# TENG.net
KiCad netlist of a schematic drawn in Altium Designer
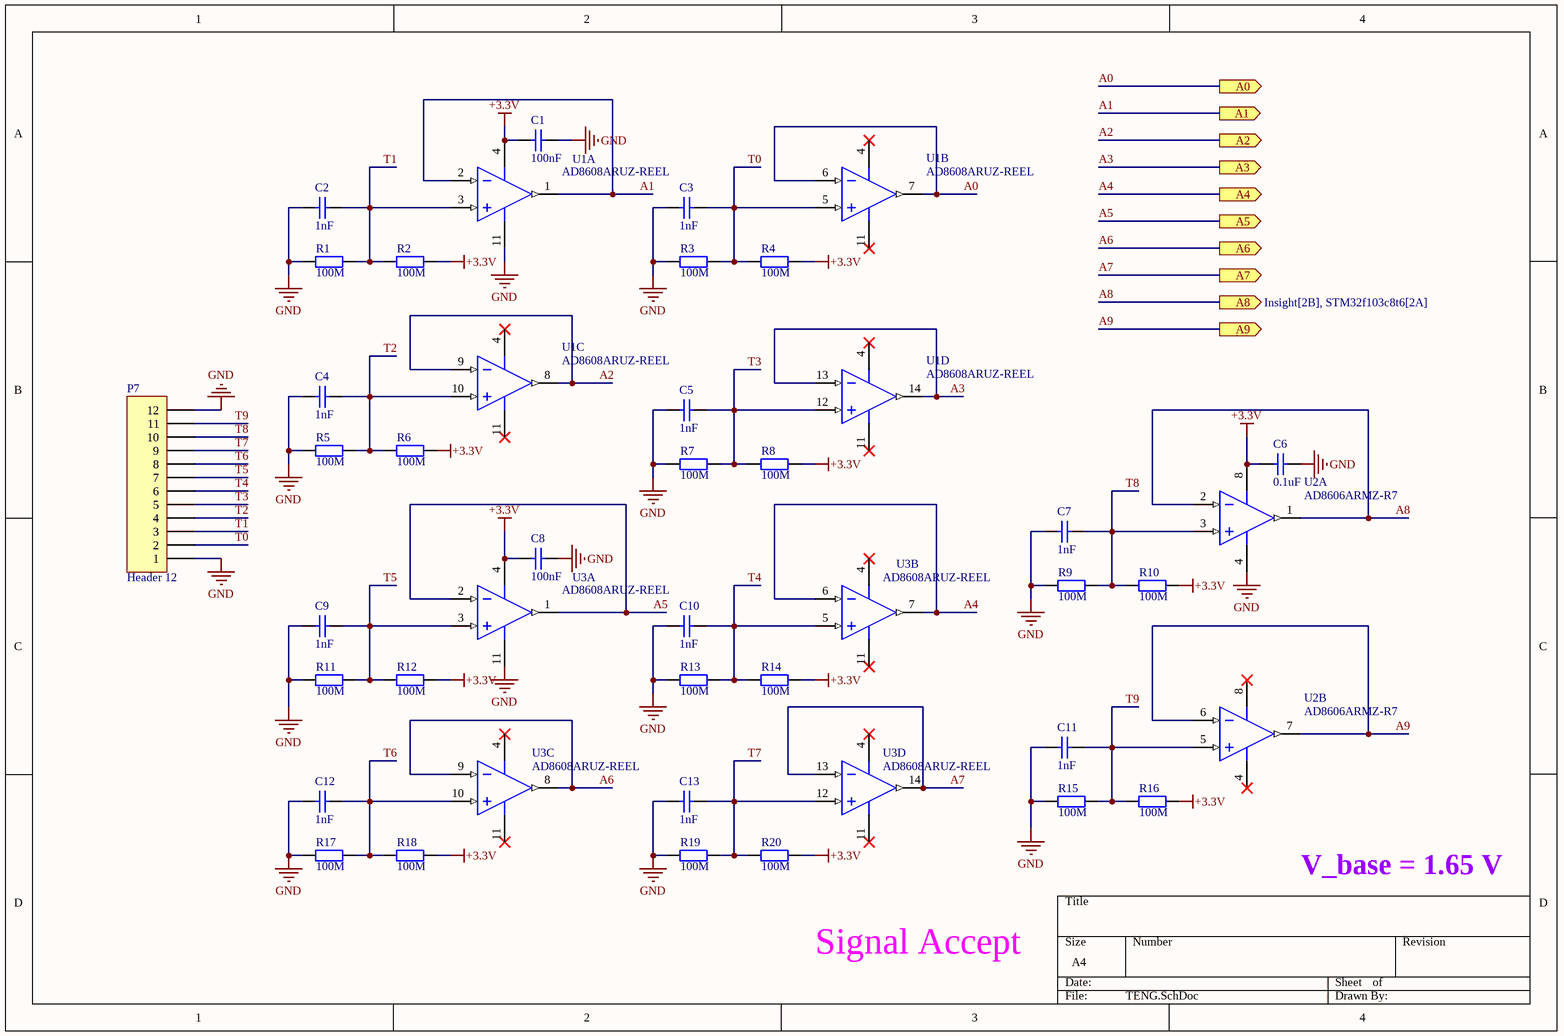
[diagram p0: TENG.SchDoc]

(export (version "E")
  (design (tool "Eeschema 10.0.6"))
  (components
    (comp (ref "C1")
      (value "100nF")
      (footprint "0402_C")
      (description "0402贴片电容")
      (libsource (lib "02-Miscellaneous_Devices_ZSF_Library") (part "Cap_0402"))
    )
    (comp (ref "C2")
      (value "1nF")
      (footprint "0402_C")
      (description "0402贴片电容")
      (libsource (lib "02-Miscellaneous_Devices_ZSF_Library") (part "Cap_0402"))
    )
    (comp (ref "C3")
      (value "1nF")
      (footprint "0402_C")
      (description "0402贴片电容")
      (libsource (lib "02-Miscellaneous_Devices_ZSF_Library") (part "Cap_0402"))
    )
    (comp (ref "C4")
      (value "1nF")
      (footprint "0402_C")
      (description "0402贴片电容")
      (libsource (lib "02-Miscellaneous_Devices_ZSF_Library") (part "Cap_0402"))
    )
    (comp (ref "C5")
      (value "1nF")
      (footprint "0402_C")
      (description "0402贴片电容")
      (libsource (lib "02-Miscellaneous_Devices_ZSF_Library") (part "Cap_0402"))
    )
    (comp (ref "C6")
      (value "0.1uF")
      (footprint "0402_C")
      (description "0402贴片电容")
      (libsource (lib "02-Miscellaneous_Devices_ZSF_Library") (part "Cap_0402"))
    )
    (comp (ref "C7")
      (value "1nF")
      (footprint "0402_C")
      (description "0402贴片电容")
      (libsource (lib "02-Miscellaneous_Devices_ZSF_Library") (part "Cap_0402"))
    )
    (comp (ref "C8")
      (value "100nF")
      (footprint "0402_C")
      (description "0402贴片电容")
      (libsource (lib "02-Miscellaneous_Devices_ZSF_Library") (part "Cap_0402"))
    )
    (comp (ref "C9")
      (value "1nF")
      (footprint "0402_C")
      (description "0402贴片电容")
      (libsource (lib "02-Miscellaneous_Devices_ZSF_Library") (part "Cap_0402"))
    )
    (comp (ref "C10")
      (value "1nF")
      (footprint "0402_C")
      (description "0402贴片电容")
      (libsource (lib "02-Miscellaneous_Devices_ZSF_Library") (part "Cap_0402"))
    )
    (comp (ref "C11")
      (value "1nF")
      (footprint "0402_C")
      (description "0402贴片电容")
      (libsource (lib "02-Miscellaneous_Devices_ZSF_Library") (part "Cap_0402"))
    )
    (comp (ref "C12")
      (value "1nF")
      (footprint "0402_C")
      (description "0402贴片电容")
      (libsource (lib "02-Miscellaneous_Devices_ZSF_Library") (part "Cap_0402"))
    )
    (comp (ref "C13")
      (value "1nF")
      (footprint "0402_C")
      (description "0402贴片电容")
      (libsource (lib "02-Miscellaneous_Devices_ZSF_Library") (part "Cap_0402"))
    )
    (comp (ref "P7")
      (value "Header 12")
      (footprint "HDR1X12")
      (description "Header, 12-Pin")
      (fields (field (name "PUBLISHER") "Altium Limited"))
      (libsource (lib "03-EButterflyIntegratedLibrary") (part "Header 12"))
    )
    (comp (ref "R1")
      (value "100M")
      (footprint "0402_R")
      (description "贴片电阻")
      (libsource (lib "02-Miscellaneous_Devices_ZSF_Library") (part "Res_0402"))
    )
    (comp (ref "R2")
      (value "100M")
      (footprint "0402_R")
      (description "贴片电阻")
      (libsource (lib "02-Miscellaneous_Devices_ZSF_Library") (part "Res_0402"))
    )
    (comp (ref "R3")
      (value "100M")
      (footprint "0402_R")
      (description "贴片电阻")
      (libsource (lib "02-Miscellaneous_Devices_ZSF_Library") (part "Res_0402"))
    )
    (comp (ref "R4")
      (value "100M")
      (footprint "0402_R")
      (description "贴片电阻")
      (libsource (lib "02-Miscellaneous_Devices_ZSF_Library") (part "Res_0402"))
    )
    (comp (ref "R5")
      (value "100M")
      (footprint "0402_R")
      (description "贴片电阻")
      (libsource (lib "02-Miscellaneous_Devices_ZSF_Library") (part "Res_0402"))
    )
    (comp (ref "R6")
      (value "100M")
      (footprint "0402_R")
      (description "贴片电阻")
      (libsource (lib "02-Miscellaneous_Devices_ZSF_Library") (part "Res_0402"))
    )
    (comp (ref "R7")
      (value "100M")
      (footprint "0402_R")
      (description "贴片电阻")
      (libsource (lib "02-Miscellaneous_Devices_ZSF_Library") (part "Res_0402"))
    )
    (comp (ref "R8")
      (value "100M")
      (footprint "0402_R")
      (description "贴片电阻")
      (libsource (lib "02-Miscellaneous_Devices_ZSF_Library") (part "Res_0402"))
    )
    (comp (ref "R9")
      (value "100M")
      (footprint "0402_R")
      (description "贴片电阻")
      (libsource (lib "02-Miscellaneous_Devices_ZSF_Library") (part "Res_0402"))
    )
    (comp (ref "R10")
      (value "100M")
      (footprint "0402_R")
      (description "贴片电阻")
      (libsource (lib "02-Miscellaneous_Devices_ZSF_Library") (part "Res_0402"))
    )
    (comp (ref "R11")
      (value "100M")
      (footprint "0402_R")
      (description "贴片电阻")
      (libsource (lib "02-Miscellaneous_Devices_ZSF_Library") (part "Res_0402"))
    )
    (comp (ref "R12")
      (value "100M")
      (footprint "0402_R")
      (description "贴片电阻")
      (libsource (lib "02-Miscellaneous_Devices_ZSF_Library") (part "Res_0402"))
    )
    (comp (ref "R13")
      (value "100M")
      (footprint "0402_R")
      (description "贴片电阻")
      (libsource (lib "02-Miscellaneous_Devices_ZSF_Library") (part "Res_0402"))
    )
    (comp (ref "R14")
      (value "100M")
      (footprint "0402_R")
      (description "贴片电阻")
      (libsource (lib "02-Miscellaneous_Devices_ZSF_Library") (part "Res_0402"))
    )
    (comp (ref "R15")
      (value "100M")
      (footprint "0402_R")
      (description "贴片电阻")
      (libsource (lib "02-Miscellaneous_Devices_ZSF_Library") (part "Res_0402"))
    )
    (comp (ref "R16")
      (value "100M")
      (footprint "0402_R")
      (description "贴片电阻")
      (libsource (lib "02-Miscellaneous_Devices_ZSF_Library") (part "Res_0402"))
    )
    (comp (ref "R17")
      (value "100M")
      (footprint "0402_R")
      (description "贴片电阻")
      (libsource (lib "02-Miscellaneous_Devices_ZSF_Library") (part "Res_0402"))
    )
    (comp (ref "R18")
      (value "100M")
      (footprint "0402_R")
      (description "贴片电阻")
      (libsource (lib "02-Miscellaneous_Devices_ZSF_Library") (part "Res_0402"))
    )
    (comp (ref "R19")
      (value "100M")
      (footprint "0402_R")
      (description "贴片电阻")
      (libsource (lib "02-Miscellaneous_Devices_ZSF_Library") (part "Res_0402"))
    )
    (comp (ref "R20")
      (value "100M")
      (footprint "0402_R")
      (description "贴片电阻")
      (libsource (lib "02-Miscellaneous_Devices_ZSF_Library") (part "Res_0402"))
    )
    (comp (ref "U1")
      (value "AD8608ARUZ-REEL")
      (footprint "ADI-RU-14_N")
      (fields (field (name "GENERIC PART NUMBER") "AD8608") (field (name "MANUFACTURER") "Analog Devices"))
      (libsource (lib "Chip") (part "AD8608-SMALL"))
    )
    (comp (ref "U2")
      (value "AD8606ARMZ-R7")
      (footprint "ADI-RM-8_N")
      (fields (field (name "GENERIC PART NUMBER") "AD8606") (field (name "MANUFACTURER") "Analog Devices"))
      (libsource (lib "Chip") (part "AD8606"))
    )
    (comp (ref "U3")
      (value "AD8608ARUZ-REEL")
      (footprint "ADI-RU-14_N")
      (fields (field (name "GENERIC PART NUMBER") "AD8608") (field (name "MANUFACTURER") "Analog Devices"))
      (libsource (lib "Chip") (part "AD8608-SMALL"))
    )
  )
  (nets
    (net (code "1") (name "+3.3V") (class "Default")
      (node (ref "C1") (pin "2") (pinfunction "2_2") (pintype "passive"))
      (node (ref "C6") (pin "2") (pinfunction "2_2") (pintype "passive"))
      (node (ref "C8") (pin "2") (pinfunction "2_2") (pintype "passive"))
      (node (ref "R10") (pin "1") (pinfunction "1_1") (pintype "passive"))
      (node (ref "R12") (pin "1") (pinfunction "1_1") (pintype "passive"))
      (node (ref "R14") (pin "1") (pinfunction "1_1") (pintype "passive"))
      (node (ref "R16") (pin "1") (pinfunction "1_1") (pintype "passive"))
      (node (ref "R18") (pin "1") (pinfunction "1_1") (pintype "passive"))
      (node (ref "R2") (pin "1") (pinfunction "1_1") (pintype "passive"))
      (node (ref "R20") (pin "1") (pinfunction "1_1") (pintype "passive"))
      (node (ref "R4") (pin "1") (pinfunction "1_1") (pintype "passive"))
      (node (ref "R6") (pin "1") (pinfunction "1_1") (pintype "passive"))
      (node (ref "R8") (pin "1") (pinfunction "1_1") (pintype "passive"))
      (node (ref "U1") (pin "4") (pinfunction "+V_4") (pintype "power_in"))
      (node (ref "U2") (pin "8") (pinfunction "+V_8") (pintype "power_in"))
      (node (ref "U3") (pin "4") (pinfunction "+V_4") (pintype "power_in"))
    )
    (net (code "2") (name "/A0") (class "Default")
      (node (ref "U1") (pin "6") (pinfunction "-IN_B_6") (pintype "input"))
      (node (ref "U1") (pin "7") (pinfunction "OUT_B_7") (pintype "output"))
    )
    (net (code "3") (name "/A1") (class "Default")
      (node (ref "U1") (pin "1") (pinfunction "OUT_A_1") (pintype "output"))
      (node (ref "U1") (pin "2") (pinfunction "-IN_A_2") (pintype "input"))
    )
    (net (code "4") (name "/A2") (class "Default")
      (node (ref "U1") (pin "8") (pinfunction "OUT_C_8") (pintype "output"))
      (node (ref "U1") (pin "9") (pinfunction "-IN_C_9") (pintype "input"))
    )
    (net (code "5") (name "/A3") (class "Default")
      (node (ref "U1") (pin "13") (pinfunction "-IN_D_13") (pintype "input"))
      (node (ref "U1") (pin "14") (pinfunction "OUT_D_14") (pintype "output"))
    )
    (net (code "6") (name "/A4") (class "Default")
      (node (ref "U3") (pin "6") (pinfunction "-IN_B_6") (pintype "input"))
      (node (ref "U3") (pin "7") (pinfunction "OUT_B_7") (pintype "output"))
    )
    (net (code "7") (name "/A5") (class "Default")
      (node (ref "U3") (pin "1") (pinfunction "OUT_A_1") (pintype "output"))
      (node (ref "U3") (pin "2") (pinfunction "-IN_A_2") (pintype "input"))
    )
    (net (code "8") (name "/A6") (class "Default")
      (node (ref "U3") (pin "8") (pinfunction "OUT_C_8") (pintype "output"))
      (node (ref "U3") (pin "9") (pinfunction "-IN_C_9") (pintype "input"))
    )
    (net (code "9") (name "/A7") (class "Default")
      (node (ref "U3") (pin "13") (pinfunction "-IN_D_13") (pintype "input"))
      (node (ref "U3") (pin "14") (pinfunction "OUT_D_14") (pintype "output"))
    )
    (net (code "10") (name "/A8") (class "Default")
      (node (ref "U2") (pin "1") (pinfunction "OUT_A_1") (pintype "output"))
      (node (ref "U2") (pin "2") (pinfunction "-IN_A_2") (pintype "input"))
    )
    (net (code "11") (name "/A9") (class "Default")
      (node (ref "U2") (pin "6") (pinfunction "-IN_B_6") (pintype "input"))
      (node (ref "U2") (pin "7") (pinfunction "OUT_B_7") (pintype "output"))
    )
    (net (code "12") (name "/T0") (class "Default")
      (node (ref "C3") (pin "1") (pinfunction "1_1") (pintype "passive"))
      (node (ref "P7") (pin "2") (pinfunction "2_2") (pintype "passive"))
      (node (ref "R3") (pin "1") (pinfunction "1_1") (pintype "passive"))
      (node (ref "R4") (pin "2") (pinfunction "2_2") (pintype "passive"))
      (node (ref "U1") (pin "5") (pinfunction "+IN_B_5") (pintype "input"))
    )
    (net (code "13") (name "/T1") (class "Default")
      (node (ref "C2") (pin "1") (pinfunction "1_1") (pintype "passive"))
      (node (ref "P7") (pin "3") (pinfunction "3_3") (pintype "passive"))
      (node (ref "R1") (pin "1") (pinfunction "1_1") (pintype "passive"))
      (node (ref "R2") (pin "2") (pinfunction "2_2") (pintype "passive"))
      (node (ref "U1") (pin "3") (pinfunction "+IN_A_3") (pintype "input"))
    )
    (net (code "14") (name "/T2") (class "Default")
      (node (ref "C4") (pin "1") (pinfunction "1_1") (pintype "passive"))
      (node (ref "P7") (pin "4") (pinfunction "4_4") (pintype "passive"))
      (node (ref "R5") (pin "1") (pinfunction "1_1") (pintype "passive"))
      (node (ref "R6") (pin "2") (pinfunction "2_2") (pintype "passive"))
      (node (ref "U1") (pin "10") (pinfunction "+IN_C_10") (pintype "input"))
    )
    (net (code "15") (name "/T3") (class "Default")
      (node (ref "C5") (pin "1") (pinfunction "1_1") (pintype "passive"))
      (node (ref "P7") (pin "5") (pinfunction "5_5") (pintype "passive"))
      (node (ref "R7") (pin "1") (pinfunction "1_1") (pintype "passive"))
      (node (ref "R8") (pin "2") (pinfunction "2_2") (pintype "passive"))
      (node (ref "U1") (pin "12") (pinfunction "+IN_D_12") (pintype "input"))
    )
    (net (code "16") (name "/T4") (class "Default")
      (node (ref "C10") (pin "1") (pinfunction "1_1") (pintype "passive"))
      (node (ref "P7") (pin "6") (pinfunction "6_6") (pintype "passive"))
      (node (ref "R13") (pin "1") (pinfunction "1_1") (pintype "passive"))
      (node (ref "R14") (pin "2") (pinfunction "2_2") (pintype "passive"))
      (node (ref "U3") (pin "5") (pinfunction "+IN_B_5") (pintype "input"))
    )
    (net (code "17") (name "/T5") (class "Default")
      (node (ref "C9") (pin "1") (pinfunction "1_1") (pintype "passive"))
      (node (ref "P7") (pin "7") (pinfunction "7_7") (pintype "passive"))
      (node (ref "R11") (pin "1") (pinfunction "1_1") (pintype "passive"))
      (node (ref "R12") (pin "2") (pinfunction "2_2") (pintype "passive"))
      (node (ref "U3") (pin "3") (pinfunction "+IN_A_3") (pintype "input"))
    )
    (net (code "18") (name "/T6") (class "Default")
      (node (ref "C12") (pin "1") (pinfunction "1_1") (pintype "passive"))
      (node (ref "P7") (pin "8") (pinfunction "8_8") (pintype "passive"))
      (node (ref "R17") (pin "1") (pinfunction "1_1") (pintype "passive"))
      (node (ref "R18") (pin "2") (pinfunction "2_2") (pintype "passive"))
      (node (ref "U3") (pin "10") (pinfunction "+IN_C_10") (pintype "input"))
    )
    (net (code "19") (name "/T7") (class "Default")
      (node (ref "C13") (pin "1") (pinfunction "1_1") (pintype "passive"))
      (node (ref "P7") (pin "9") (pinfunction "9_9") (pintype "passive"))
      (node (ref "R19") (pin "1") (pinfunction "1_1") (pintype "passive"))
      (node (ref "R20") (pin "2") (pinfunction "2_2") (pintype "passive"))
      (node (ref "U3") (pin "12") (pinfunction "+IN_D_12") (pintype "input"))
    )
    (net (code "20") (name "/T8") (class "Default")
      (node (ref "C7") (pin "1") (pinfunction "1_1") (pintype "passive"))
      (node (ref "P7") (pin "10") (pinfunction "10_10") (pintype "passive"))
      (node (ref "R10") (pin "2") (pinfunction "2_2") (pintype "passive"))
      (node (ref "R9") (pin "1") (pinfunction "1_1") (pintype "passive"))
      (node (ref "U2") (pin "3") (pinfunction "+IN_A_3") (pintype "input"))
    )
    (net (code "21") (name "/T9") (class "Default")
      (node (ref "C11") (pin "1") (pinfunction "1_1") (pintype "passive"))
      (node (ref "P7") (pin "11") (pinfunction "11_11") (pintype "passive"))
      (node (ref "R15") (pin "1") (pinfunction "1_1") (pintype "passive"))
      (node (ref "R16") (pin "2") (pinfunction "2_2") (pintype "passive"))
      (node (ref "U2") (pin "5") (pinfunction "+IN_B_5") (pintype "input"))
    )
    (net (code "22") (name "GND") (class "Default")
      (node (ref "C1") (pin "1") (pinfunction "1_1") (pintype "passive"))
      (node (ref "C10") (pin "2") (pinfunction "2_2") (pintype "passive"))
      (node (ref "C11") (pin "2") (pinfunction "2_2") (pintype "passive"))
      (node (ref "C12") (pin "2") (pinfunction "2_2") (pintype "passive"))
      (node (ref "C13") (pin "2") (pinfunction "2_2") (pintype "passive"))
      (node (ref "C2") (pin "2") (pinfunction "2_2") (pintype "passive"))
      (node (ref "C3") (pin "2") (pinfunction "2_2") (pintype "passive"))
      (node (ref "C4") (pin "2") (pinfunction "2_2") (pintype "passive"))
      (node (ref "C5") (pin "2") (pinfunction "2_2") (pintype "passive"))
      (node (ref "C6") (pin "1") (pinfunction "1_1") (pintype "passive"))
      (node (ref "C7") (pin "2") (pinfunction "2_2") (pintype "passive"))
      (node (ref "C8") (pin "1") (pinfunction "1_1") (pintype "passive"))
      (node (ref "C9") (pin "2") (pinfunction "2_2") (pintype "passive"))
      (node (ref "P7") (pin "1") (pinfunction "1_1") (pintype "passive"))
      (node (ref "P7") (pin "12") (pinfunction "12_12") (pintype "passive"))
      (node (ref "R1") (pin "2") (pinfunction "2_2") (pintype "passive"))
      (node (ref "R11") (pin "2") (pinfunction "2_2") (pintype "passive"))
      (node (ref "R13") (pin "2") (pinfunction "2_2") (pintype "passive"))
      (node (ref "R15") (pin "2") (pinfunction "2_2") (pintype "passive"))
      (node (ref "R17") (pin "2") (pinfunction "2_2") (pintype "passive"))
      (node (ref "R19") (pin "2") (pinfunction "2_2") (pintype "passive"))
      (node (ref "R3") (pin "2") (pinfunction "2_2") (pintype "passive"))
      (node (ref "R5") (pin "2") (pinfunction "2_2") (pintype "passive"))
      (node (ref "R7") (pin "2") (pinfunction "2_2") (pintype "passive"))
      (node (ref "R9") (pin "2") (pinfunction "2_2") (pintype "passive"))
      (node (ref "U1") (pin "11") (pinfunction "-V_11") (pintype "power_in"))
      (node (ref "U2") (pin "4") (pinfunction "-V_4") (pintype "power_in"))
      (node (ref "U3") (pin "11") (pinfunction "-V_11") (pintype "power_in"))
    )
    (net (code "23") (name "unconnected-(U1B-+V-Pad4)") (class "Default")
      (node (ref "U1") (pin "4") (pinfunction "+V_4") (pintype "power_in+no_connect"))
    )
    (net (code "24") (name "unconnected-(U1B--V-Pad11)") (class "Default")
      (node (ref "U1") (pin "11") (pinfunction "-V_11") (pintype "power_in+no_connect"))
    )
    (net (code "25") (name "unconnected-(U1C-+V-Pad4)") (class "Default")
      (node (ref "U1") (pin "4") (pinfunction "+V_4") (pintype "power_in+no_connect"))
    )
    (net (code "26") (name "unconnected-(U1C--V-Pad11)") (class "Default")
      (node (ref "U1") (pin "11") (pinfunction "-V_11") (pintype "power_in+no_connect"))
    )
    (net (code "27") (name "unconnected-(U1D-+V-Pad4)") (class "Default")
      (node (ref "U1") (pin "4") (pinfunction "+V_4") (pintype "power_in+no_connect"))
    )
    (net (code "28") (name "unconnected-(U1D--V-Pad11)") (class "Default")
      (node (ref "U1") (pin "11") (pinfunction "-V_11") (pintype "power_in+no_connect"))
    )
    (net (code "29") (name "unconnected-(U2B-+V-Pad8)") (class "Default")
      (node (ref "U2") (pin "8") (pinfunction "+V_8") (pintype "power_in+no_connect"))
    )
    (net (code "30") (name "unconnected-(U2B--V-Pad4)") (class "Default")
      (node (ref "U2") (pin "4") (pinfunction "-V_4") (pintype "power_in+no_connect"))
    )
    (net (code "31") (name "unconnected-(U3B-+V-Pad4)") (class "Default")
      (node (ref "U3") (pin "4") (pinfunction "+V_4") (pintype "power_in+no_connect"))
    )
    (net (code "32") (name "unconnected-(U3B--V-Pad11)") (class "Default")
      (node (ref "U3") (pin "11") (pinfunction "-V_11") (pintype "power_in+no_connect"))
    )
    (net (code "33") (name "unconnected-(U3C-+V-Pad4)") (class "Default")
      (node (ref "U3") (pin "4") (pinfunction "+V_4") (pintype "power_in+no_connect"))
    )
    (net (code "34") (name "unconnected-(U3C--V-Pad11)") (class "Default")
      (node (ref "U3") (pin "11") (pinfunction "-V_11") (pintype "power_in+no_connect"))
    )
    (net (code "35") (name "unconnected-(U3D-+V-Pad4)") (class "Default")
      (node (ref "U3") (pin "4") (pinfunction "+V_4") (pintype "power_in+no_connect"))
    )
    (net (code "36") (name "unconnected-(U3D--V-Pad11)") (class "Default")
      (node (ref "U3") (pin "11") (pinfunction "-V_11") (pintype "power_in+no_connect"))
    )
  )
)
